# RoDAP.net
KiCad netlist of a schematic drawn in EAGLE
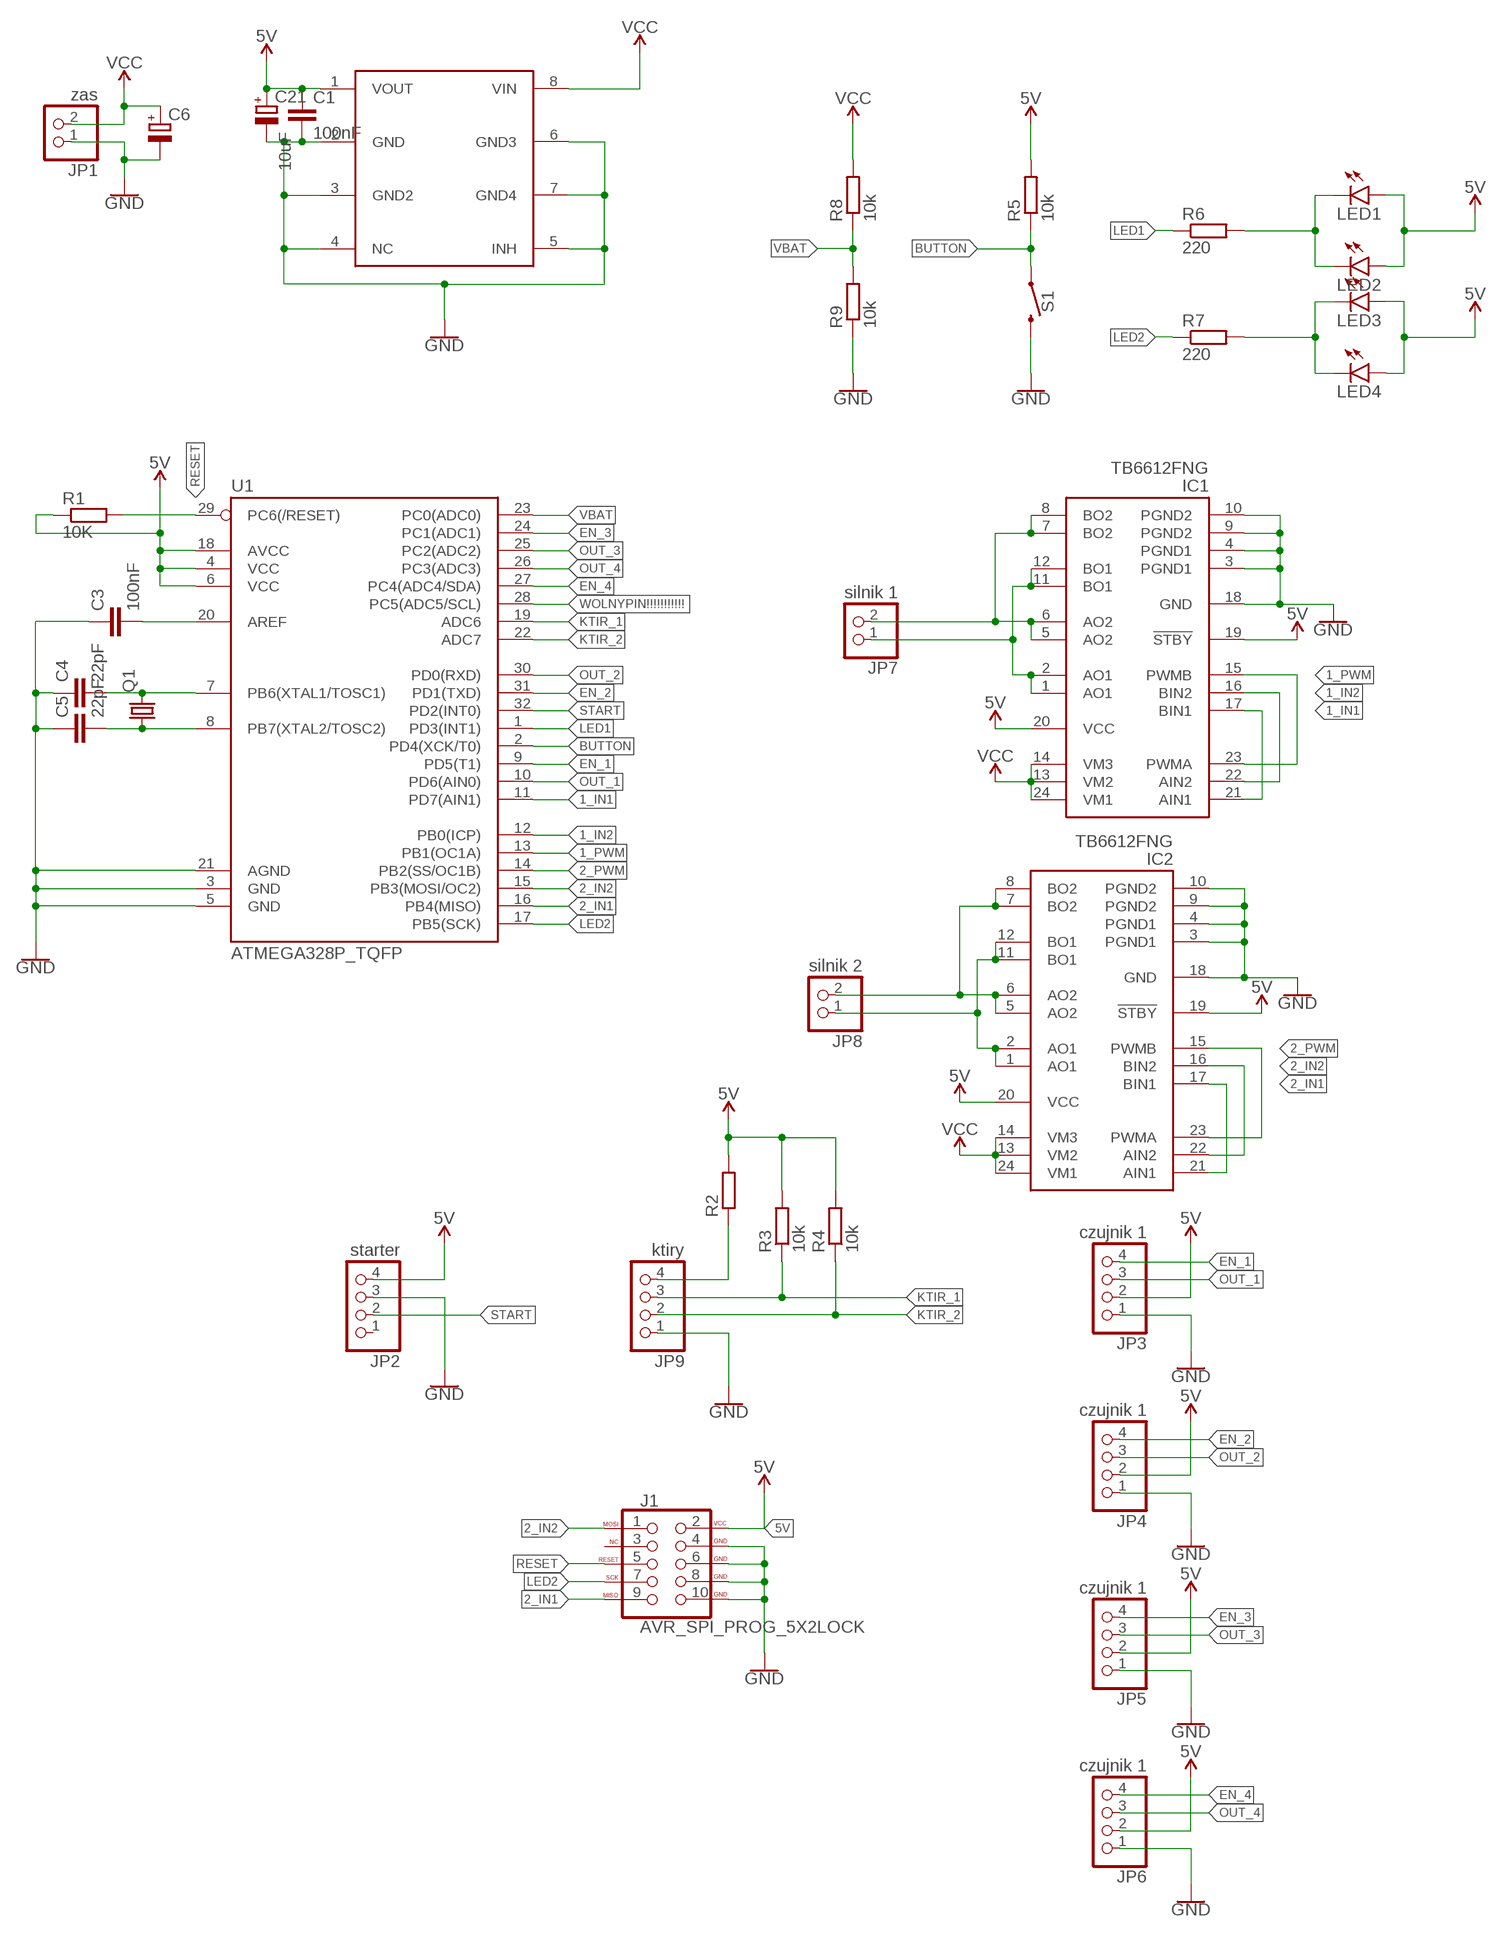
[diagram p0: schematic, sheet 1]

(export (version "E")
  (design (tool "Eeschema 10.0.6"))
  (components
    (comp (ref "C1")
      (value "100nF")
      (footprint "eagle-import:C0805")
      (libsource (lib "eagle-import") (part "C-EUC0805"))
    )
    (comp (ref "C3")
      (value "100nF")
      (footprint "eagle-import:C0805")
      (libsource (lib "eagle-import") (part "C-EUC0805"))
    )
    (comp (ref "C4")
      (value "22pF")
      (footprint "eagle-import:C0805")
      (libsource (lib "eagle-import") (part "C-EUC0805"))
    )
    (comp (ref "C5")
      (value "22pF")
      (footprint "eagle-import:C0805")
      (libsource (lib "eagle-import") (part "C-EUC0805"))
    )
    (comp (ref "C6")
      (value "CPOL-EUE2.5-7")
      (footprint "eagle-import:E2,5-7")
      (libsource (lib "eagle-import") (part "CPOL-EUE2.5-7"))
    )
    (comp (ref "C21")
      (value "10uF")
      (footprint "eagle-import:SMC_B")
      (libsource (lib "eagle-import") (part "CPOL-EUSMCB"))
    )
    (comp (ref "IC1")
      (value "TB6612FNG")
      (footprint "eagle-import:SSOP24")
      (libsource (lib "eagle-import") (part "TB6612FNG"))
    )
    (comp (ref "IC2")
      (value "TB6612FNG")
      (footprint "eagle-import:SSOP24")
      (libsource (lib "eagle-import") (part "TB6612FNG"))
    )
    (comp (ref "J1")
      (value "AVR_SPI_PROG_5X2LOCK")
      (footprint "eagle-import:2X5-SHROUDED_LOCK")
      (libsource (lib "eagle-import") (part "AVR_SPI_PROG_5X2LOCK"))
    )
    (comp (ref "JP1")
      (value "zas")
      (footprint "eagle-import:1X02")
      (libsource (lib "eagle-import") (part "PINHD-1X2"))
    )
    (comp (ref "JP2")
      (value "starter")
      (footprint "eagle-import:1X04")
      (libsource (lib "eagle-import") (part "PINHD-1X4"))
    )
    (comp (ref "JP3")
      (value "czujnik 1")
      (footprint "eagle-import:1X04")
      (libsource (lib "eagle-import") (part "PINHD-1X4"))
    )
    (comp (ref "JP4")
      (value "czujnik 1")
      (footprint "eagle-import:1X04")
      (libsource (lib "eagle-import") (part "PINHD-1X4"))
    )
    (comp (ref "JP5")
      (value "czujnik 1")
      (footprint "eagle-import:1X04")
      (libsource (lib "eagle-import") (part "PINHD-1X4"))
    )
    (comp (ref "JP6")
      (value "czujnik 1")
      (footprint "eagle-import:1X04")
      (libsource (lib "eagle-import") (part "PINHD-1X4"))
    )
    (comp (ref "JP7")
      (value "silnik 1")
      (footprint "eagle-import:1X02")
      (libsource (lib "eagle-import") (part "PINHD-1X2"))
    )
    (comp (ref "JP8")
      (value "silnik 2")
      (footprint "eagle-import:1X02")
      (libsource (lib "eagle-import") (part "PINHD-1X2"))
    )
    (comp (ref "JP9")
      (value "ktiry")
      (footprint "eagle-import:1X04")
      (libsource (lib "eagle-import") (part "PINHD-1X4"))
    )
    (comp (ref "LED1")
      (value "LED5MM")
      (footprint "eagle-import:LED5MM")
      (libsource (lib "eagle-import") (part "LED5MM"))
    )
    (comp (ref "LED2")
      (value "LEDSML0805")
      (footprint "eagle-import:SML0805")
      (libsource (lib "eagle-import") (part "LEDSML0805"))
    )
    (comp (ref "LED3")
      (value "LED5MM")
      (footprint "eagle-import:LED5MM")
      (libsource (lib "eagle-import") (part "LED5MM"))
    )
    (comp (ref "LED4")
      (value "LEDSML0805")
      (footprint "eagle-import:SML0805")
      (libsource (lib "eagle-import") (part "LEDSML0805"))
    )
    (comp (ref "Q1")
      (value "CRYSTALHC49S")
      (footprint "eagle-import:HC49_S")
      (libsource (lib "eagle-import") (part "CRYSTALHC49S"))
    )
    (comp (ref "R1")
      (value "10K")
      (footprint "eagle-import:R0805")
      (libsource (lib "eagle-import") (part "R-EU_R0805"))
    )
    (comp (ref "R2")
      (value "R-EU_R0805")
      (footprint "eagle-import:R0805")
      (libsource (lib "eagle-import") (part "R-EU_R0805"))
    )
    (comp (ref "R3")
      (value "10k")
      (footprint "eagle-import:R0805")
      (libsource (lib "eagle-import") (part "R-EU_R0805"))
    )
    (comp (ref "R4")
      (value "10k")
      (footprint "eagle-import:R0805")
      (libsource (lib "eagle-import") (part "R-EU_R0805"))
    )
    (comp (ref "R5")
      (value "10k")
      (footprint "eagle-import:R0805")
      (libsource (lib "eagle-import") (part "R-EU_R0805"))
    )
    (comp (ref "R6")
      (value "220")
      (footprint "eagle-import:R0805")
      (libsource (lib "eagle-import") (part "R-EU_R0805"))
    )
    (comp (ref "R7")
      (value "220")
      (footprint "eagle-import:R0805")
      (libsource (lib "eagle-import") (part "R-EU_R0805"))
    )
    (comp (ref "R8")
      (value "10k")
      (footprint "eagle-import:R0805")
      (libsource (lib "eagle-import") (part "R-EU_R0805"))
    )
    (comp (ref "R9")
      (value "10k")
      (footprint "eagle-import:R0805")
      (libsource (lib "eagle-import") (part "R-EU_R0805"))
    )
    (comp (ref "S1")
      (value "MOMENTARY-SWITCH-SPST-SMD-6.0X3.5MM")
      (footprint "eagle-import:TACTILE_SWITCH_SMD_6.0X3.5MM")
      (libsource (lib "eagle-import") (part "MOMENTARY-SWITCH-SPST-SMD-6.0X3.5MM"))
    )
    (comp (ref "U$4")
      (value "KF50BD-TR")
      (footprint "eagle-import:SOIC8-1.27-5X4MM")
      (libsource (lib "eagle-import") (part "KF50BD-TR"))
    )
    (comp (ref "U1")
      (value "ATMEGA328P_TQFP")
      (footprint "eagle-import:TQFP32-08")
      (libsource (lib "eagle-import") (part "ATMEGA328P_TQFP"))
    )
  )
  (nets
    (net (code "1") (name "/WOLNYPIN~~~~~~{}") (class "Default")
      (node (ref "U1") (pin "28") (pinfunction "PC5(ADC5/SCL)_28") (pintype "bidirectional"))
    )
    (net (code "2") (name "1_IN1") (class "Default")
      (node (ref "IC1") (pin "17") (pinfunction "BIN1_17") (pintype "bidirectional"))
      (node (ref "IC1") (pin "21") (pinfunction "AIN1_21") (pintype "bidirectional"))
      (node (ref "U1") (pin "11") (pinfunction "PD7(AIN1)_11") (pintype "bidirectional"))
    )
    (net (code "3") (name "1_IN2") (class "Default")
      (node (ref "IC1") (pin "16") (pinfunction "BIN2_16") (pintype "bidirectional"))
      (node (ref "IC1") (pin "22") (pinfunction "AIN2_22") (pintype "bidirectional"))
      (node (ref "U1") (pin "12") (pinfunction "PB0(ICP)_12") (pintype "bidirectional"))
    )
    (net (code "4") (name "1_PWM") (class "Default")
      (node (ref "IC1") (pin "15") (pinfunction "PWMB_15") (pintype "bidirectional"))
      (node (ref "IC1") (pin "23") (pinfunction "PWMA_23") (pintype "bidirectional"))
      (node (ref "U1") (pin "13") (pinfunction "PB1(OC1A)_13") (pintype "bidirectional"))
    )
    (net (code "5") (name "2_IN1") (class "Default")
      (node (ref "IC2") (pin "17") (pinfunction "BIN1_17") (pintype "bidirectional"))
      (node (ref "IC2") (pin "21") (pinfunction "AIN1_21") (pintype "bidirectional"))
      (node (ref "J1") (pin "9") (pinfunction "MISO_9") (pintype "passive"))
      (node (ref "U1") (pin "16") (pinfunction "PB4(MISO)_16") (pintype "bidirectional"))
    )
    (net (code "6") (name "2_IN2") (class "Default")
      (node (ref "IC2") (pin "16") (pinfunction "BIN2_16") (pintype "bidirectional"))
      (node (ref "IC2") (pin "22") (pinfunction "AIN2_22") (pintype "bidirectional"))
      (node (ref "J1") (pin "1") (pinfunction "MOSI_1") (pintype "passive"))
      (node (ref "U1") (pin "15") (pinfunction "PB3(MOSI/OC2)_15") (pintype "bidirectional"))
    )
    (net (code "7") (name "2_PWM") (class "Default")
      (node (ref "IC2") (pin "15") (pinfunction "PWMB_15") (pintype "bidirectional"))
      (node (ref "IC2") (pin "23") (pinfunction "PWMA_23") (pintype "bidirectional"))
      (node (ref "U1") (pin "14") (pinfunction "PB2(SS/OC1B)_14") (pintype "bidirectional"))
    )
    (net (code "8") (name "5V") (class "Default")
      (node (ref "C1") (pin "1") (pinfunction "1_1") (pintype "passive"))
      (node (ref "C21") (pin "+") (pinfunction "+_+") (pintype "passive"))
      (node (ref "IC1") (pin "19") (pinfunction "~{STBY}_19") (pintype "bidirectional"))
      (node (ref "IC1") (pin "20") (pinfunction "VCC_20") (pintype "bidirectional"))
      (node (ref "IC2") (pin "19") (pinfunction "~{STBY}_19") (pintype "bidirectional"))
      (node (ref "IC2") (pin "20") (pinfunction "VCC_20") (pintype "bidirectional"))
      (node (ref "J1") (pin "2") (pinfunction "VCC_2") (pintype "power_in"))
      (node (ref "JP2") (pin "4") (pinfunction "4_4") (pintype "passive"))
      (node (ref "JP3") (pin "2") (pinfunction "2_2") (pintype "passive"))
      (node (ref "JP4") (pin "2") (pinfunction "2_2") (pintype "passive"))
      (node (ref "JP5") (pin "2") (pinfunction "2_2") (pintype "passive"))
      (node (ref "JP6") (pin "2") (pinfunction "2_2") (pintype "passive"))
      (node (ref "LED1") (pin "A") (pinfunction "A_A") (pintype "passive"))
      (node (ref "LED2") (pin "A") (pinfunction "A_A") (pintype "passive"))
      (node (ref "LED3") (pin "A") (pinfunction "A_A") (pintype "passive"))
      (node (ref "LED4") (pin "A") (pinfunction "A_A") (pintype "passive"))
      (node (ref "R1") (pin "1") (pinfunction "1_1") (pintype "passive"))
      (node (ref "R2") (pin "2") (pinfunction "2_2") (pintype "passive"))
      (node (ref "R3") (pin "2") (pinfunction "2_2") (pintype "passive"))
      (node (ref "R4") (pin "2") (pinfunction "2_2") (pintype "passive"))
      (node (ref "R5") (pin "2") (pinfunction "2_2") (pintype "passive"))
      (node (ref "U$4") (pin "1") (pinfunction "VOUT_1") (pintype "bidirectional"))
      (node (ref "U1") (pin "18") (pinfunction "AVCC_18") (pintype "bidirectional"))
      (node (ref "U1") (pin "4") (pinfunction "VCC_4") (pintype "bidirectional"))
      (node (ref "U1") (pin "6") (pinfunction "VCC_6") (pintype "bidirectional"))
    )
    (net (code "9") (name "BUTTON") (class "Default")
      (node (ref "R5") (pin "1") (pinfunction "1_1") (pintype "passive"))
      (node (ref "S1") (pin "1") (pinfunction "1_1") (pintype "passive"))
      (node (ref "U1") (pin "2") (pinfunction "PD4(XCK/T0)_2") (pintype "bidirectional"))
    )
    (net (code "10") (name "EN_1") (class "Default")
      (node (ref "JP3") (pin "4") (pinfunction "4_4") (pintype "passive"))
      (node (ref "U1") (pin "9") (pinfunction "PD5(T1)_9") (pintype "bidirectional"))
    )
    (net (code "11") (name "EN_2") (class "Default")
      (node (ref "JP4") (pin "4") (pinfunction "4_4") (pintype "passive"))
      (node (ref "U1") (pin "31") (pinfunction "PD1(TXD)_31") (pintype "bidirectional"))
    )
    (net (code "12") (name "EN_3") (class "Default")
      (node (ref "JP5") (pin "4") (pinfunction "4_4") (pintype "passive"))
      (node (ref "U1") (pin "24") (pinfunction "PC1(ADC1)_24") (pintype "bidirectional"))
    )
    (net (code "13") (name "EN_4") (class "Default")
      (node (ref "JP6") (pin "4") (pinfunction "4_4") (pintype "passive"))
      (node (ref "U1") (pin "27") (pinfunction "PC4(ADC4/SDA)_27") (pintype "bidirectional"))
    )
    (net (code "14") (name "GND") (class "Default")
      (node (ref "C1") (pin "2") (pinfunction "2_2") (pintype "passive"))
      (node (ref "C21") (pin "-") (pinfunction "-_-") (pintype "passive"))
      (node (ref "C3") (pin "1") (pinfunction "1_1") (pintype "passive"))
      (node (ref "C4") (pin "1") (pinfunction "1_1") (pintype "passive"))
      (node (ref "C5") (pin "1") (pinfunction "1_1") (pintype "passive"))
      (node (ref "C6") (pin "-") (pinfunction "-_-") (pintype "passive"))
      (node (ref "IC1") (pin "10") (pinfunction "PGND2_10") (pintype "bidirectional"))
      (node (ref "IC1") (pin "18") (pinfunction "GND_18") (pintype "bidirectional"))
      (node (ref "IC1") (pin "3") (pinfunction "PGND1_3") (pintype "bidirectional"))
      (node (ref "IC1") (pin "4") (pinfunction "PGND1_4") (pintype "bidirectional"))
      (node (ref "IC1") (pin "9") (pinfunction "PGND2_9") (pintype "bidirectional"))
      (node (ref "IC2") (pin "10") (pinfunction "PGND2_10") (pintype "bidirectional"))
      (node (ref "IC2") (pin "18") (pinfunction "GND_18") (pintype "bidirectional"))
      (node (ref "IC2") (pin "3") (pinfunction "PGND1_3") (pintype "bidirectional"))
      (node (ref "IC2") (pin "4") (pinfunction "PGND1_4") (pintype "bidirectional"))
      (node (ref "IC2") (pin "9") (pinfunction "PGND2_9") (pintype "bidirectional"))
      (node (ref "J1") (pin "10") (pinfunction "GND_10") (pintype "power_in"))
      (node (ref "J1") (pin "4") (pinfunction "GND_4") (pintype "power_in"))
      (node (ref "J1") (pin "6") (pinfunction "GND_6") (pintype "power_in"))
      (node (ref "J1") (pin "8") (pinfunction "GND_8") (pintype "power_in"))
      (node (ref "JP1") (pin "1") (pinfunction "1_1") (pintype "passive"))
      (node (ref "JP2") (pin "3") (pinfunction "3_3") (pintype "passive"))
      (node (ref "JP3") (pin "1") (pinfunction "1_1") (pintype "passive"))
      (node (ref "JP4") (pin "1") (pinfunction "1_1") (pintype "passive"))
      (node (ref "JP5") (pin "1") (pinfunction "1_1") (pintype "passive"))
      (node (ref "JP6") (pin "1") (pinfunction "1_1") (pintype "passive"))
      (node (ref "JP9") (pin "1") (pinfunction "1_1") (pintype "passive"))
      (node (ref "R9") (pin "1") (pinfunction "1_1") (pintype "passive"))
      (node (ref "S1") (pin "2") (pinfunction "2_2") (pintype "passive"))
      (node (ref "U$4") (pin "2") (pinfunction "GND_2") (pintype "bidirectional"))
      (node (ref "U$4") (pin "3") (pinfunction "GND2_3") (pintype "bidirectional"))
      (node (ref "U$4") (pin "4") (pinfunction "NC_4") (pintype "bidirectional"))
      (node (ref "U$4") (pin "5") (pinfunction "INH_5") (pintype "bidirectional"))
      (node (ref "U$4") (pin "6") (pinfunction "GND3_6") (pintype "bidirectional"))
      (node (ref "U$4") (pin "7") (pinfunction "GND4_7") (pintype "bidirectional"))
      (node (ref "U1") (pin "21") (pinfunction "AGND_21") (pintype "bidirectional"))
      (node (ref "U1") (pin "3") (pinfunction "GND_3") (pintype "bidirectional"))
      (node (ref "U1") (pin "5") (pinfunction "GND_5") (pintype "bidirectional"))
    )
    (net (code "15") (name "KTIR_1") (class "Default")
      (node (ref "JP9") (pin "3") (pinfunction "3_3") (pintype "passive"))
      (node (ref "R3") (pin "1") (pinfunction "1_1") (pintype "passive"))
      (node (ref "U1") (pin "19") (pinfunction "ADC6_19") (pintype "bidirectional"))
    )
    (net (code "16") (name "KTIR_2") (class "Default")
      (node (ref "JP9") (pin "2") (pinfunction "2_2") (pintype "passive"))
      (node (ref "R4") (pin "1") (pinfunction "1_1") (pintype "passive"))
      (node (ref "U1") (pin "22") (pinfunction "ADC7_22") (pintype "bidirectional"))
    )
    (net (code "17") (name "LED1") (class "Default")
      (node (ref "R6") (pin "1") (pinfunction "1_1") (pintype "passive"))
      (node (ref "U1") (pin "1") (pinfunction "PD3(INT1)_1") (pintype "bidirectional"))
    )
    (net (code "18") (name "LED2") (class "Default")
      (node (ref "J1") (pin "7") (pinfunction "SCK_7") (pintype "passive"))
      (node (ref "R7") (pin "1") (pinfunction "1_1") (pintype "passive"))
      (node (ref "U1") (pin "17") (pinfunction "PB5(SCK)_17") (pintype "bidirectional"))
    )
    (net (code "19") (name "Net-(IC1-AO1-Pad1)") (class "Default")
      (node (ref "IC1") (pin "1") (pinfunction "AO1_1") (pintype "bidirectional"))
      (node (ref "IC1") (pin "11") (pinfunction "BO1_11") (pintype "bidirectional"))
      (node (ref "IC1") (pin "12") (pinfunction "BO1_12") (pintype "bidirectional"))
      (node (ref "IC1") (pin "2") (pinfunction "AO1_2") (pintype "bidirectional"))
      (node (ref "JP7") (pin "1") (pinfunction "1_1") (pintype "passive"))
    )
    (net (code "20") (name "Net-(IC1-AO2-Pad5)") (class "Default")
      (node (ref "IC1") (pin "5") (pinfunction "AO2_5") (pintype "bidirectional"))
      (node (ref "IC1") (pin "6") (pinfunction "AO2_6") (pintype "bidirectional"))
      (node (ref "IC1") (pin "7") (pinfunction "BO2_7") (pintype "bidirectional"))
      (node (ref "IC1") (pin "8") (pinfunction "BO2_8") (pintype "bidirectional"))
      (node (ref "JP7") (pin "2") (pinfunction "2_2") (pintype "passive"))
    )
    (net (code "21") (name "Net-(IC2-AO1-Pad1)") (class "Default")
      (node (ref "IC2") (pin "1") (pinfunction "AO1_1") (pintype "bidirectional"))
      (node (ref "IC2") (pin "11") (pinfunction "BO1_11") (pintype "bidirectional"))
      (node (ref "IC2") (pin "12") (pinfunction "BO1_12") (pintype "bidirectional"))
      (node (ref "IC2") (pin "2") (pinfunction "AO1_2") (pintype "bidirectional"))
      (node (ref "JP8") (pin "1") (pinfunction "1_1") (pintype "passive"))
    )
    (net (code "22") (name "Net-(IC2-AO2-Pad5)") (class "Default")
      (node (ref "IC2") (pin "5") (pinfunction "AO2_5") (pintype "bidirectional"))
      (node (ref "IC2") (pin "6") (pinfunction "AO2_6") (pintype "bidirectional"))
      (node (ref "IC2") (pin "7") (pinfunction "BO2_7") (pintype "bidirectional"))
      (node (ref "IC2") (pin "8") (pinfunction "BO2_8") (pintype "bidirectional"))
      (node (ref "JP8") (pin "2") (pinfunction "2_2") (pintype "passive"))
    )
    (net (code "23") (name "Net-(JP9-Pad4)") (class "Default")
      (node (ref "JP9") (pin "4") (pinfunction "4_4") (pintype "passive"))
      (node (ref "R2") (pin "1") (pinfunction "1_1") (pintype "passive"))
    )
    (net (code "24") (name "Net-(LED1-C)") (class "Default")
      (node (ref "LED1") (pin "K") (pinfunction "C_K") (pintype "passive"))
      (node (ref "LED2") (pin "C") (pinfunction "C_C") (pintype "passive"))
      (node (ref "R6") (pin "2") (pinfunction "2_2") (pintype "passive"))
    )
    (net (code "25") (name "Net-(LED3-C)") (class "Default")
      (node (ref "LED3") (pin "K") (pinfunction "C_K") (pintype "passive"))
      (node (ref "LED4") (pin "C") (pinfunction "C_C") (pintype "passive"))
      (node (ref "R7") (pin "2") (pinfunction "2_2") (pintype "passive"))
    )
    (net (code "26") (name "Net-(U1-AREF)") (class "Default")
      (node (ref "C3") (pin "2") (pinfunction "2_2") (pintype "passive"))
      (node (ref "U1") (pin "20") (pinfunction "AREF_20") (pintype "bidirectional"))
    )
    (net (code "27") (name "Net-(U1-PB6(XTAL1{slash}TOSC1))") (class "Default")
      (node (ref "C4") (pin "2") (pinfunction "2_2") (pintype "passive"))
      (node (ref "Q1") (pin "2") (pinfunction "2_2") (pintype "passive"))
      (node (ref "U1") (pin "7") (pinfunction "PB6(XTAL1/TOSC1)_7") (pintype "bidirectional"))
    )
    (net (code "28") (name "Net-(U1-PB7(XTAL2{slash}TOSC2))") (class "Default")
      (node (ref "C5") (pin "2") (pinfunction "2_2") (pintype "passive"))
      (node (ref "Q1") (pin "1") (pinfunction "1_1") (pintype "passive"))
      (node (ref "U1") (pin "8") (pinfunction "PB7(XTAL2/TOSC2)_8") (pintype "bidirectional"))
    )
    (net (code "29") (name "OUT_1") (class "Default")
      (node (ref "JP3") (pin "3") (pinfunction "3_3") (pintype "passive"))
      (node (ref "U1") (pin "10") (pinfunction "PD6(AIN0)_10") (pintype "bidirectional"))
    )
    (net (code "30") (name "OUT_2") (class "Default")
      (node (ref "JP4") (pin "3") (pinfunction "3_3") (pintype "passive"))
      (node (ref "U1") (pin "30") (pinfunction "PD0(RXD)_30") (pintype "bidirectional"))
    )
    (net (code "31") (name "OUT_3") (class "Default")
      (node (ref "JP5") (pin "3") (pinfunction "3_3") (pintype "passive"))
      (node (ref "U1") (pin "25") (pinfunction "PC2(ADC2)_25") (pintype "bidirectional"))
    )
    (net (code "32") (name "OUT_4") (class "Default")
      (node (ref "JP6") (pin "3") (pinfunction "3_3") (pintype "passive"))
      (node (ref "U1") (pin "26") (pinfunction "PC3(ADC3)_26") (pintype "bidirectional"))
    )
    (net (code "33") (name "RESET") (class "Default")
      (node (ref "J1") (pin "5") (pinfunction "RESET_5") (pintype "passive"))
      (node (ref "R1") (pin "2") (pinfunction "2_2") (pintype "passive"))
      (node (ref "U1") (pin "29") (pinfunction "PC6(/RESET)_29") (pintype "bidirectional"))
    )
    (net (code "34") (name "START") (class "Default")
      (node (ref "JP2") (pin "2") (pinfunction "2_2") (pintype "passive"))
      (node (ref "U1") (pin "32") (pinfunction "PD2(INT0)_32") (pintype "bidirectional"))
    )
    (net (code "35") (name "VBAT") (class "Default")
      (node (ref "R8") (pin "1") (pinfunction "1_1") (pintype "passive"))
      (node (ref "R9") (pin "2") (pinfunction "2_2") (pintype "passive"))
      (node (ref "U1") (pin "23") (pinfunction "PC0(ADC0)_23") (pintype "bidirectional"))
    )
    (net (code "36") (name "VCC") (class "Default")
      (node (ref "C6") (pin "+") (pinfunction "+_+") (pintype "passive"))
      (node (ref "IC1") (pin "13") (pinfunction "VM2_13") (pintype "bidirectional"))
      (node (ref "IC1") (pin "14") (pinfunction "VM3_14") (pintype "bidirectional"))
      (node (ref "IC1") (pin "24") (pinfunction "VM1_24") (pintype "bidirectional"))
      (node (ref "IC2") (pin "13") (pinfunction "VM2_13") (pintype "bidirectional"))
      (node (ref "IC2") (pin "14") (pinfunction "VM3_14") (pintype "bidirectional"))
      (node (ref "IC2") (pin "24") (pinfunction "VM1_24") (pintype "bidirectional"))
      (node (ref "JP1") (pin "2") (pinfunction "2_2") (pintype "passive"))
      (node (ref "R8") (pin "2") (pinfunction "2_2") (pintype "passive"))
      (node (ref "U$4") (pin "8") (pinfunction "VIN_8") (pintype "bidirectional"))
    )
    (net (code "37") (name "unconnected-(J1-NC-Pad3)") (class "Default")
      (node (ref "J1") (pin "3") (pinfunction "NC_3") (pintype "no_connect"))
    )
    (net (code "38") (name "unconnected-(JP2-Pad1)") (class "Default")
      (node (ref "JP2") (pin "1") (pinfunction "1_1") (pintype "passive"))
    )
  )
)
